# radio-86rk-SRAM-sdcard.net
KiCad netlist of a schematic drawn in EAGLE
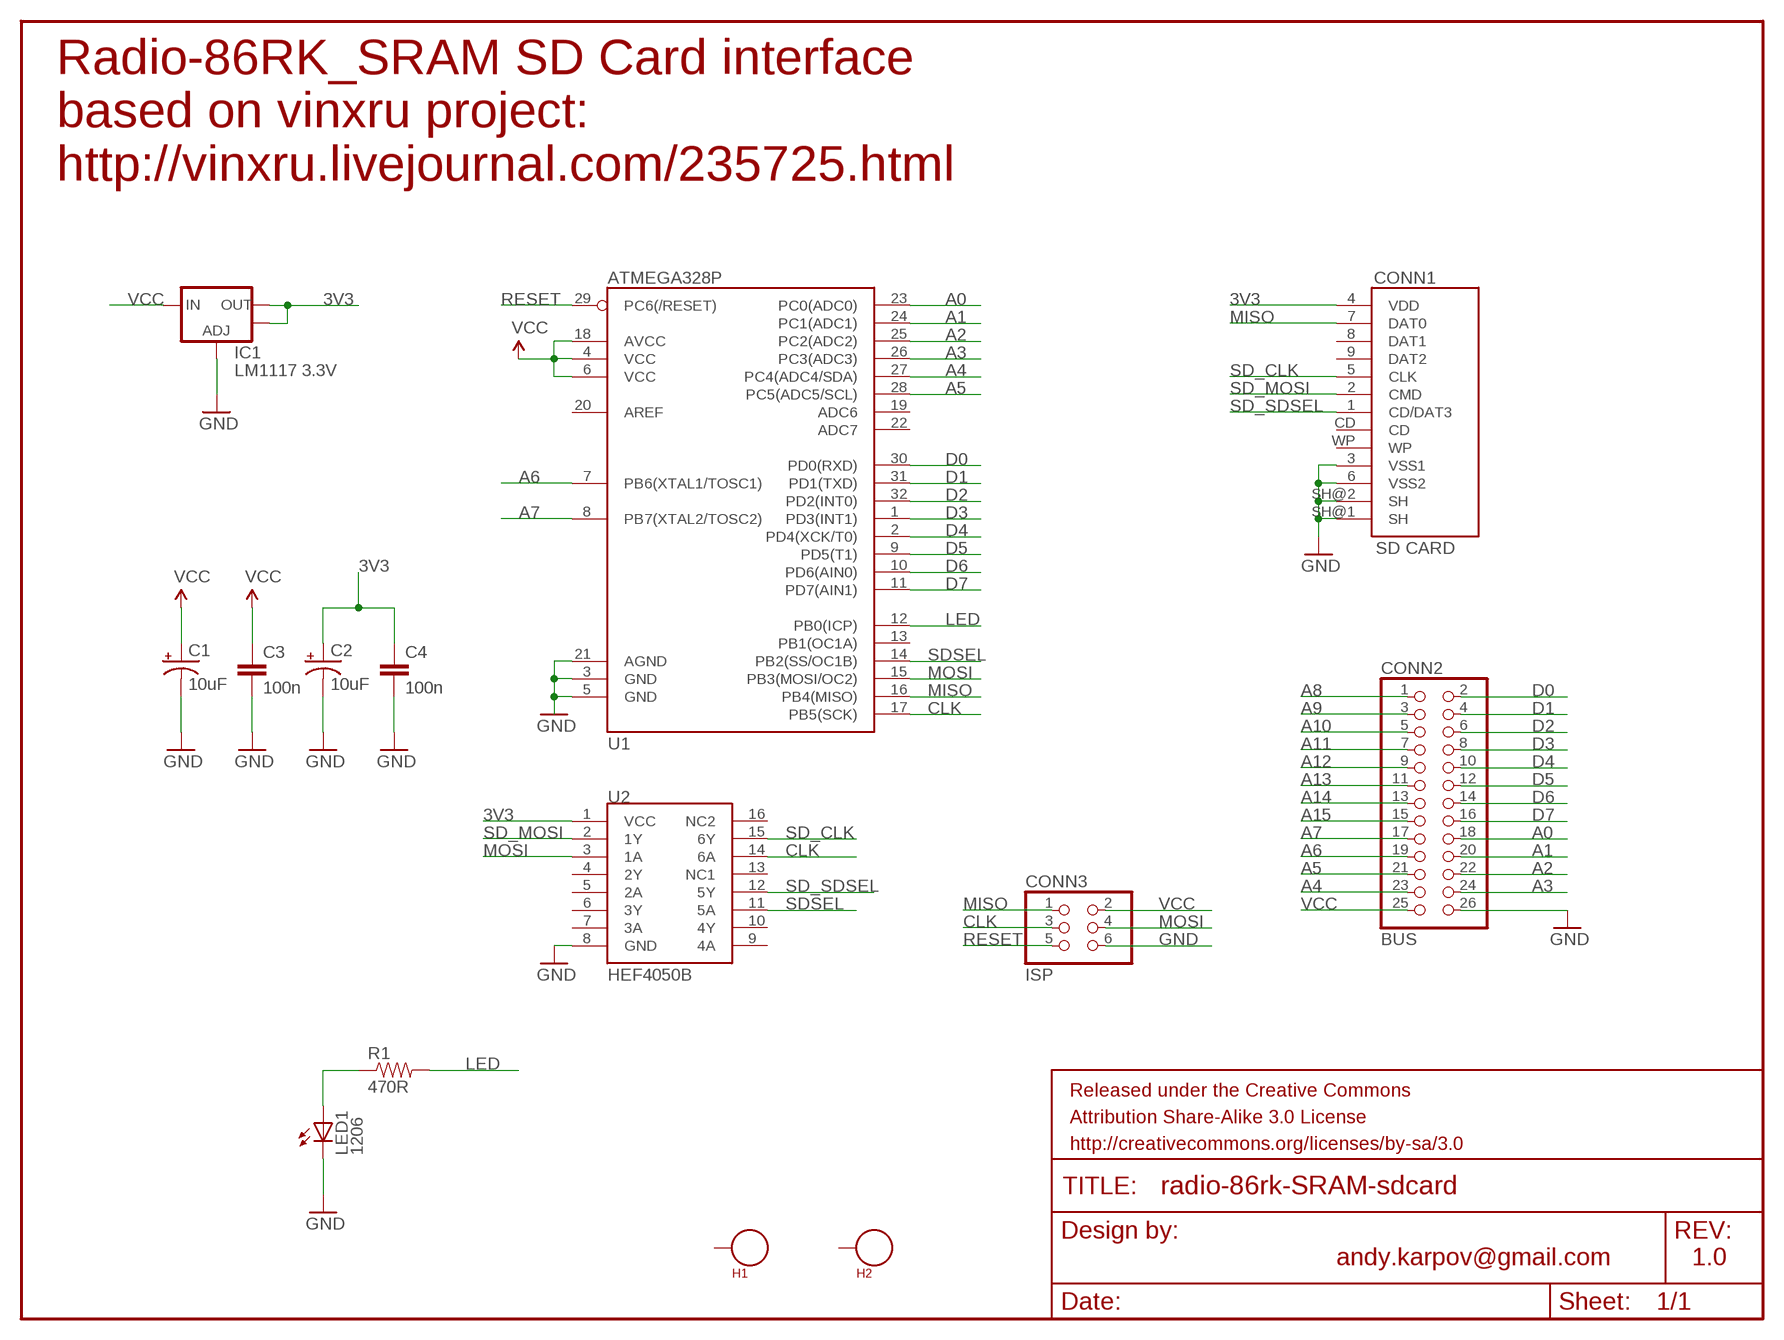
[diagram p0: schematic, sheet 1]

(export (version "E")
  (design (tool "Eeschema 10.0.6"))
  (components
    (comp (ref "C1")
      (value "10uF")
      (footprint "eagle-import:EIA3216")
      (libsource (lib "eagle-import") (part "10UF-16V-10%(TANT)"))
    )
    (comp (ref "C2")
      (value "10uF")
      (footprint "eagle-import:EIA3216")
      (libsource (lib "eagle-import") (part "10UF-16V-10%(TANT)"))
    )
    (comp (ref "C3")
      (value "100n")
      (footprint "eagle-import:1206")
      (libsource (lib "eagle-import") (part "CAP1206"))
    )
    (comp (ref "C4")
      (value "100n")
      (footprint "eagle-import:1206")
      (libsource (lib "eagle-import") (part "CAP1206"))
    )
    (comp (ref "CONN1")
      (value "SD CARD")
      (footprint "eagle-import:SDCARD_4UCONN")
      (libsource (lib "eagle-import") (part "SD_CARD_SOCKET4UCON"))
    )
    (comp (ref "CONN2")
      (value "BUS")
      (footprint "eagle-import:2X13")
      (libsource (lib "eagle-import") (part "PINHD-2X13"))
    )
    (comp (ref "CONN3")
      (value "ISP")
      (footprint "eagle-import:2X03")
      (libsource (lib "eagle-import") (part "PINHD-2X3"))
    )
    (comp (ref "FRAME1")
      (value "FRAME-LETTER")
      (footprint "eagle-import:CREATIVE_COMMONS")
      (libsource (lib "eagle-import") (part "FRAME-LETTER"))
    )
    (comp (ref "H1")
      (value "SEW_HOLE")
      (footprint "eagle-import:SIMPLE_HOLE")
      (libsource (lib "eagle-import") (part "SEW_HOLE"))
    )
    (comp (ref "H2")
      (value "SEW_HOLE")
      (footprint "eagle-import:SIMPLE_HOLE")
      (libsource (lib "eagle-import") (part "SEW_HOLE"))
    )
    (comp (ref "IC1")
      (value "LM1117 3.3V")
      (footprint "eagle-import:SOT223")
      (libsource (lib "eagle-import") (part "V_REG_LM1117SOT223"))
    )
    (comp (ref "LED1")
      (value "1206")
      (footprint "eagle-import:CHIPLED_1206")
      (libsource (lib "eagle-import") (part "LEDCHIPLED_1206"))
    )
    (comp (ref "R1")
      (value "470R")
      (footprint "eagle-import:1206")
      (libsource (lib "eagle-import") (part "RESISTOR1206"))
    )
    (comp (ref "U1")
      (value "ATMEGA328P")
      (footprint "eagle-import:TQFP32-08")
      (libsource (lib "eagle-import") (part "ATMEGA328_SMT"))
    )
    (comp (ref "U2")
      (value "HEF4050B")
      (footprint "eagle-import:SO16")
      (libsource (lib "eagle-import") (part "HEF4050BSO16"))
    )
  )
  (nets
    (net (code "1") (name "/3V3") (class "Default")
      (node (ref "C2") (pin "A") (pinfunction "+_A") (pintype "passive"))
      (node (ref "C4") (pin "1") (pinfunction "1_1") (pintype "passive"))
      (node (ref "CONN1") (pin "4") (pinfunction "VDD_4") (pintype "power_in"))
      (node (ref "IC1") (pin "2") (pinfunction "OUT_2") (pintype "output"))
      (node (ref "IC1") (pin "4") (pinfunction "OUT_4") (pintype "output"))
      (node (ref "U2") (pin "1") (pinfunction "VCC_1") (pintype "power_in"))
    )
    (net (code "2") (name "/A0") (class "Default")
      (node (ref "CONN2") (pin "18") (pinfunction "18_18") (pintype "passive"))
      (node (ref "U1") (pin "23") (pinfunction "PC0(ADC0)_23") (pintype "bidirectional"))
    )
    (net (code "3") (name "/A1") (class "Default")
      (node (ref "CONN2") (pin "20") (pinfunction "20_20") (pintype "passive"))
      (node (ref "U1") (pin "24") (pinfunction "PC1(ADC1)_24") (pintype "bidirectional"))
    )
    (net (code "4") (name "/A2") (class "Default")
      (node (ref "CONN2") (pin "22") (pinfunction "22_22") (pintype "passive"))
      (node (ref "U1") (pin "25") (pinfunction "PC2(ADC2)_25") (pintype "bidirectional"))
    )
    (net (code "5") (name "/A3") (class "Default")
      (node (ref "CONN2") (pin "24") (pinfunction "24_24") (pintype "passive"))
      (node (ref "U1") (pin "26") (pinfunction "PC3(ADC3)_26") (pintype "bidirectional"))
    )
    (net (code "6") (name "/A4") (class "Default")
      (node (ref "CONN2") (pin "23") (pinfunction "23_23") (pintype "passive"))
      (node (ref "U1") (pin "27") (pinfunction "PC4(ADC4/SDA)_27") (pintype "bidirectional"))
    )
    (net (code "7") (name "/A5") (class "Default")
      (node (ref "CONN2") (pin "21") (pinfunction "21_21") (pintype "passive"))
      (node (ref "U1") (pin "28") (pinfunction "PC5(ADC5/SCL)_28") (pintype "bidirectional"))
    )
    (net (code "8") (name "/A6") (class "Default")
      (node (ref "CONN2") (pin "19") (pinfunction "19_19") (pintype "passive"))
      (node (ref "U1") (pin "7") (pinfunction "PB6(XTAL1/TOSC1)_7") (pintype "bidirectional"))
    )
    (net (code "9") (name "/A7") (class "Default")
      (node (ref "CONN2") (pin "17") (pinfunction "17_17") (pintype "passive"))
      (node (ref "U1") (pin "8") (pinfunction "PB7(XTAL2/TOSC2)_8") (pintype "bidirectional"))
    )
    (net (code "10") (name "/A8") (class "Default")
      (node (ref "CONN2") (pin "1") (pinfunction "1_1") (pintype "passive"))
    )
    (net (code "11") (name "/A9") (class "Default")
      (node (ref "CONN2") (pin "3") (pinfunction "3_3") (pintype "passive"))
    )
    (net (code "12") (name "/A10") (class "Default")
      (node (ref "CONN2") (pin "5") (pinfunction "5_5") (pintype "passive"))
    )
    (net (code "13") (name "/A11") (class "Default")
      (node (ref "CONN2") (pin "7") (pinfunction "7_7") (pintype "passive"))
    )
    (net (code "14") (name "/A12") (class "Default")
      (node (ref "CONN2") (pin "9") (pinfunction "9_9") (pintype "passive"))
    )
    (net (code "15") (name "/A13") (class "Default")
      (node (ref "CONN2") (pin "11") (pinfunction "11_11") (pintype "passive"))
    )
    (net (code "16") (name "/A14") (class "Default")
      (node (ref "CONN2") (pin "13") (pinfunction "13_13") (pintype "passive"))
    )
    (net (code "17") (name "/A15") (class "Default")
      (node (ref "CONN2") (pin "15") (pinfunction "15_15") (pintype "passive"))
    )
    (net (code "18") (name "/CLK") (class "Default")
      (node (ref "CONN3") (pin "3") (pinfunction "3_3") (pintype "passive"))
      (node (ref "U1") (pin "17") (pinfunction "PB5(SCK)_17") (pintype "bidirectional"))
      (node (ref "U2") (pin "14") (pinfunction "6A_14") (pintype "input"))
    )
    (net (code "19") (name "/D0") (class "Default")
      (node (ref "CONN2") (pin "2") (pinfunction "2_2") (pintype "passive"))
      (node (ref "U1") (pin "30") (pinfunction "PD0(RXD)_30") (pintype "bidirectional"))
    )
    (net (code "20") (name "/D1") (class "Default")
      (node (ref "CONN2") (pin "4") (pinfunction "4_4") (pintype "passive"))
      (node (ref "U1") (pin "31") (pinfunction "PD1(TXD)_31") (pintype "bidirectional"))
    )
    (net (code "21") (name "/D2") (class "Default")
      (node (ref "CONN2") (pin "6") (pinfunction "6_6") (pintype "passive"))
      (node (ref "U1") (pin "32") (pinfunction "PD2(INT0)_32") (pintype "bidirectional"))
    )
    (net (code "22") (name "/D3") (class "Default")
      (node (ref "CONN2") (pin "8") (pinfunction "8_8") (pintype "passive"))
      (node (ref "U1") (pin "1") (pinfunction "PD3(INT1)_1") (pintype "bidirectional"))
    )
    (net (code "23") (name "/D4") (class "Default")
      (node (ref "CONN2") (pin "10") (pinfunction "10_10") (pintype "passive"))
      (node (ref "U1") (pin "2") (pinfunction "PD4(XCK/T0)_2") (pintype "bidirectional"))
    )
    (net (code "24") (name "/D5") (class "Default")
      (node (ref "CONN2") (pin "12") (pinfunction "12_12") (pintype "passive"))
      (node (ref "U1") (pin "9") (pinfunction "PD5(T1)_9") (pintype "bidirectional"))
    )
    (net (code "25") (name "/D6") (class "Default")
      (node (ref "CONN2") (pin "14") (pinfunction "14_14") (pintype "passive"))
      (node (ref "U1") (pin "10") (pinfunction "PD6(AIN0)_10") (pintype "bidirectional"))
    )
    (net (code "26") (name "/D7") (class "Default")
      (node (ref "CONN2") (pin "16") (pinfunction "16_16") (pintype "passive"))
      (node (ref "U1") (pin "11") (pinfunction "PD7(AIN1)_11") (pintype "bidirectional"))
    )
    (net (code "27") (name "/LED") (class "Default")
      (node (ref "R1") (pin "2") (pinfunction "2_2") (pintype "passive"))
      (node (ref "U1") (pin "12") (pinfunction "PB0(ICP)_12") (pintype "bidirectional"))
    )
    (net (code "28") (name "/MISO") (class "Default")
      (node (ref "CONN1") (pin "7") (pinfunction "DAT0_7") (pintype "bidirectional"))
      (node (ref "CONN3") (pin "1") (pinfunction "1_1") (pintype "passive"))
      (node (ref "U1") (pin "16") (pinfunction "PB4(MISO)_16") (pintype "bidirectional"))
    )
    (net (code "29") (name "/MOSI") (class "Default")
      (node (ref "CONN3") (pin "4") (pinfunction "4_4") (pintype "passive"))
      (node (ref "U1") (pin "15") (pinfunction "PB3(MOSI/OC2)_15") (pintype "bidirectional"))
      (node (ref "U2") (pin "3") (pinfunction "1A_3") (pintype "input"))
    )
    (net (code "30") (name "/RESET") (class "Default")
      (node (ref "CONN3") (pin "5") (pinfunction "5_5") (pintype "passive"))
      (node (ref "U1") (pin "29") (pinfunction "PC6(/RESET)_29") (pintype "bidirectional"))
    )
    (net (code "31") (name "/SDSEL") (class "Default")
      (node (ref "U1") (pin "14") (pinfunction "PB2(SS/OC1B)_14") (pintype "bidirectional"))
      (node (ref "U2") (pin "11") (pinfunction "5A_11") (pintype "input"))
    )
    (net (code "32") (name "/SD_CLK") (class "Default")
      (node (ref "CONN1") (pin "5") (pinfunction "CLK_5") (pintype "bidirectional"))
      (node (ref "U2") (pin "15") (pinfunction "6Y_15") (pintype "output"))
    )
    (net (code "33") (name "/SD_MOSI") (class "Default")
      (node (ref "CONN1") (pin "2") (pinfunction "CMD_2") (pintype "bidirectional"))
      (node (ref "U2") (pin "2") (pinfunction "1Y_2") (pintype "output"))
    )
    (net (code "34") (name "/SD_SDSEL") (class "Default")
      (node (ref "CONN1") (pin "1") (pinfunction "CD/DAT3_1") (pintype "bidirectional"))
      (node (ref "U2") (pin "12") (pinfunction "5Y_12") (pintype "output"))
    )
    (net (code "35") (name "GND") (class "Default")
      (node (ref "C1") (pin "C") (pinfunction "-_C") (pintype "passive"))
      (node (ref "C2") (pin "C") (pinfunction "-_C") (pintype "passive"))
      (node (ref "C3") (pin "2") (pinfunction "2_2") (pintype "passive"))
      (node (ref "C4") (pin "2") (pinfunction "2_2") (pintype "passive"))
      (node (ref "CONN1") (pin "3") (pinfunction "VSS1_3") (pintype "power_in"))
      (node (ref "CONN1") (pin "6") (pinfunction "VSS2_6") (pintype "power_in"))
      (node (ref "CONN1") (pin "SH@1") (pinfunction "SH_SH@1") (pintype "bidirectional"))
      (node (ref "CONN1") (pin "SH@2") (pinfunction "SH_SH@2") (pintype "bidirectional"))
      (node (ref "CONN2") (pin "26") (pinfunction "26_26") (pintype "passive"))
      (node (ref "CONN3") (pin "6") (pinfunction "6_6") (pintype "passive"))
      (node (ref "IC1") (pin "1") (pinfunction "ADJ_1") (pintype "input"))
      (node (ref "LED1") (pin "C") (pinfunction "C_C") (pintype "passive"))
      (node (ref "U1") (pin "21") (pinfunction "AGND_21") (pintype "bidirectional"))
      (node (ref "U1") (pin "3") (pinfunction "GND_3") (pintype "bidirectional"))
      (node (ref "U1") (pin "5") (pinfunction "GND_5") (pintype "bidirectional"))
      (node (ref "U2") (pin "8") (pinfunction "GND_8") (pintype "power_in"))
    )
    (net (code "36") (name "Net-(LED1-PadA)") (class "Default")
      (node (ref "LED1") (pin "A") (pinfunction "A_A") (pintype "passive"))
      (node (ref "R1") (pin "1") (pinfunction "1_1") (pintype "passive"))
    )
    (net (code "37") (name "VCC") (class "Default")
      (node (ref "C1") (pin "A") (pinfunction "+_A") (pintype "passive"))
      (node (ref "C3") (pin "1") (pinfunction "1_1") (pintype "passive"))
      (node (ref "CONN2") (pin "25") (pinfunction "25_25") (pintype "passive"))
      (node (ref "CONN3") (pin "2") (pinfunction "2_2") (pintype "passive"))
      (node (ref "IC1") (pin "3") (pinfunction "IN_3") (pintype "input"))
      (node (ref "U1") (pin "18") (pinfunction "AVCC_18") (pintype "bidirectional"))
      (node (ref "U1") (pin "4") (pinfunction "VCC_4") (pintype "bidirectional"))
      (node (ref "U1") (pin "6") (pinfunction "VCC_6") (pintype "bidirectional"))
    )
    (net (code "38") (name "unconnected-(CONN1-DAT1-Pad8)") (class "Default")
      (node (ref "CONN1") (pin "8") (pinfunction "DAT1_8") (pintype "bidirectional"))
    )
    (net (code "39") (name "unconnected-(CONN1-DAT2-Pad9)") (class "Default")
      (node (ref "CONN1") (pin "9") (pinfunction "DAT2_9") (pintype "bidirectional"))
    )
    (net (code "40") (name "unconnected-(CONN1-PadCD)") (class "Default")
      (node (ref "CONN1") (pin "CD") (pinfunction "CD_CD") (pintype "bidirectional"))
    )
    (net (code "41") (name "unconnected-(CONN1-PadWP)") (class "Default")
      (node (ref "CONN1") (pin "WP") (pinfunction "WP_WP") (pintype "bidirectional"))
    )
    (net (code "42") (name "unconnected-(H1-PadP$1)") (class "Default")
      (node (ref "H1") (pin "P$1") (pinfunction "P$1_P$1") (pintype "bidirectional"))
    )
    (net (code "43") (name "unconnected-(H2-PadP$1)") (class "Default")
      (node (ref "H2") (pin "P$1") (pinfunction "P$1_P$1") (pintype "bidirectional"))
    )
    (net (code "44") (name "unconnected-(U1-ADC6-Pad19)") (class "Default")
      (node (ref "U1") (pin "19") (pinfunction "ADC6_19") (pintype "bidirectional"))
    )
    (net (code "45") (name "unconnected-(U1-ADC7-Pad22)") (class "Default")
      (node (ref "U1") (pin "22") (pinfunction "ADC7_22") (pintype "bidirectional"))
    )
    (net (code "46") (name "unconnected-(U1-AREF-Pad20)") (class "Default")
      (node (ref "U1") (pin "20") (pinfunction "AREF_20") (pintype "bidirectional"))
    )
    (net (code "47") (name "unconnected-(U1-PB1(OC1A)-Pad13)") (class "Default")
      (node (ref "U1") (pin "13") (pinfunction "PB1(OC1A)_13") (pintype "bidirectional"))
    )
    (net (code "48") (name "unconnected-(U2-2A-Pad5)") (class "Default")
      (node (ref "U2") (pin "5") (pinfunction "2A_5") (pintype "input"))
    )
    (net (code "49") (name "unconnected-(U2-2Y-Pad4)") (class "Default")
      (node (ref "U2") (pin "4") (pinfunction "2Y_4") (pintype "output"))
    )
    (net (code "50") (name "unconnected-(U2-3A-Pad7)") (class "Default")
      (node (ref "U2") (pin "7") (pinfunction "3A_7") (pintype "input"))
    )
    (net (code "51") (name "unconnected-(U2-3Y-Pad6)") (class "Default")
      (node (ref "U2") (pin "6") (pinfunction "3Y_6") (pintype "output"))
    )
    (net (code "52") (name "unconnected-(U2-4A-Pad9)") (class "Default")
      (node (ref "U2") (pin "9") (pinfunction "4A_9") (pintype "input"))
    )
    (net (code "53") (name "unconnected-(U2-4Y-Pad10)") (class "Default")
      (node (ref "U2") (pin "10") (pinfunction "4Y_10") (pintype "output"))
    )
    (net (code "54") (name "unconnected-(U2-NC1-Pad13)") (class "Default")
      (node (ref "U2") (pin "13") (pinfunction "NC1_13") (pintype "no_connect"))
    )
    (net (code "55") (name "unconnected-(U2-NC2-Pad16)") (class "Default")
      (node (ref "U2") (pin "16") (pinfunction "NC2_16") (pintype "no_connect"))
    )
  )
)
